# G3-Sensor.net
KiCad netlist of a schematic drawn in Altium Designer
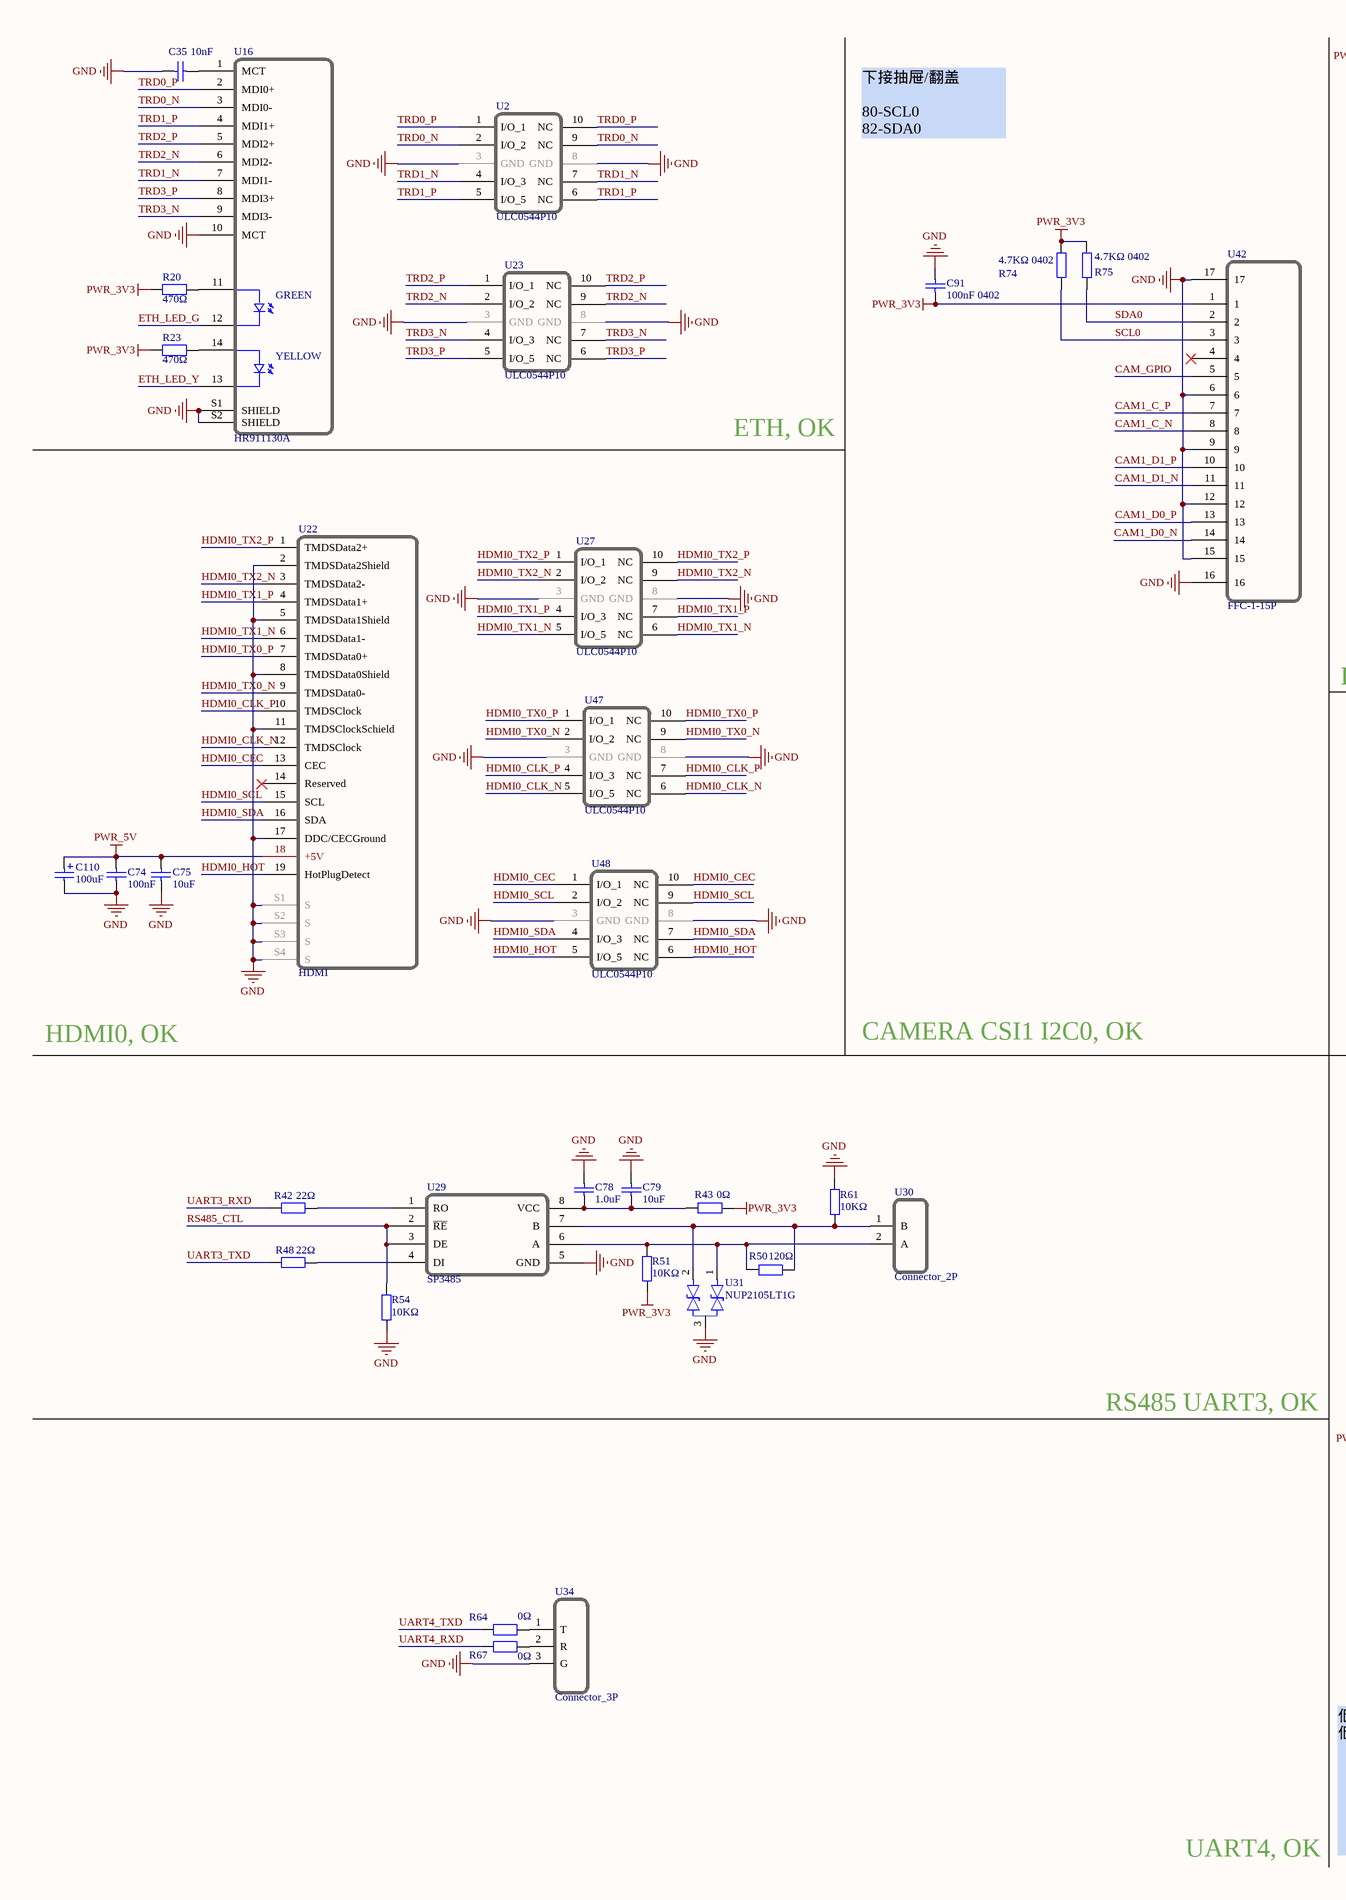
[diagram p0: G3-Sensor.SchDoc, left]
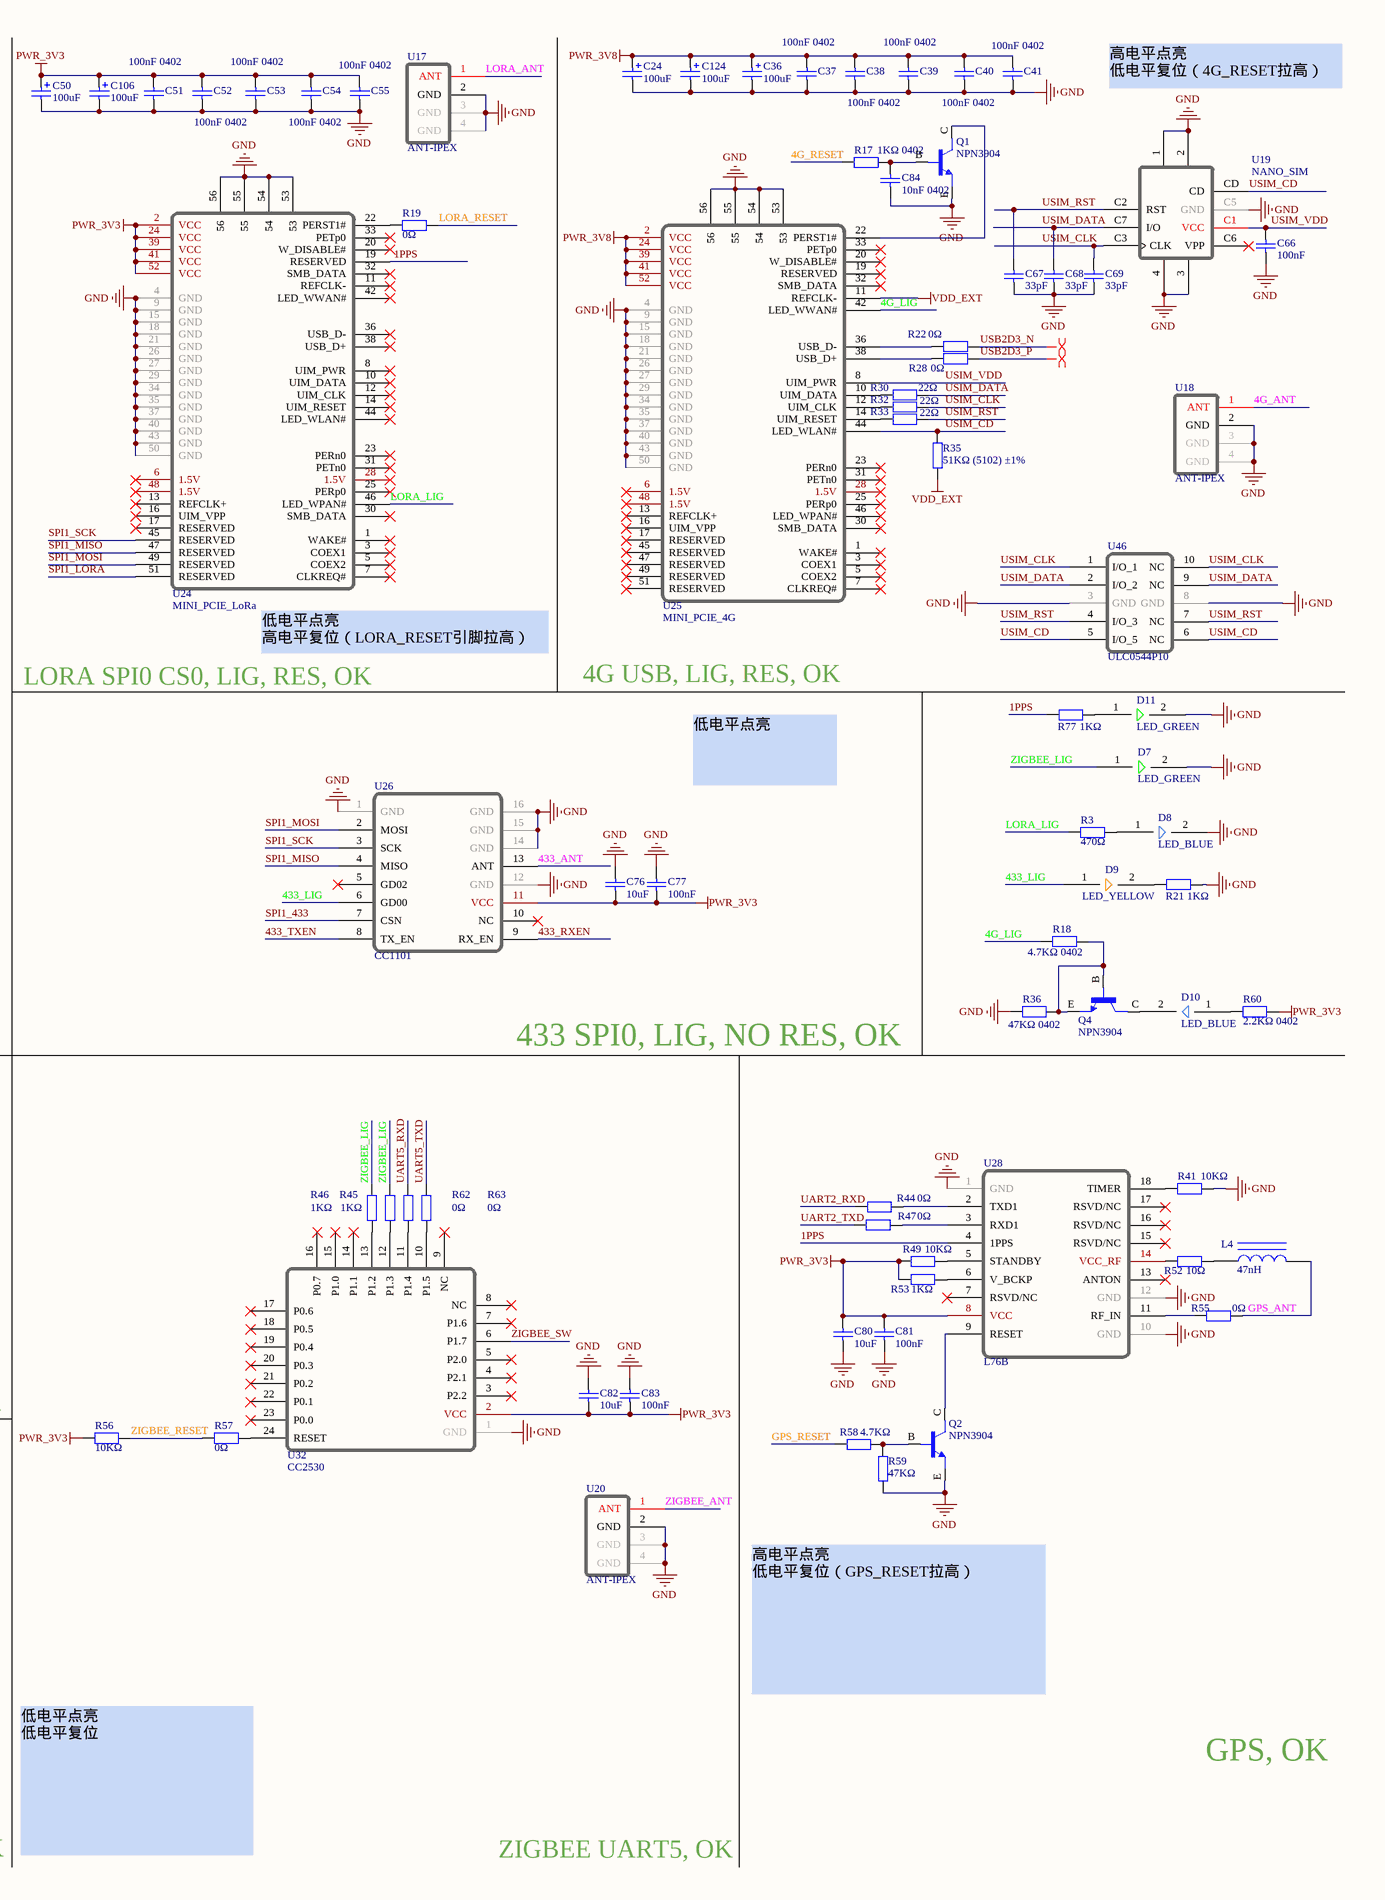
[diagram p1: G3-Sensor.SchDoc, right]

(export (version "E")
  (design (tool "Eeschema 10.0.6"))
  (components
    (comp (ref "C24")
      (value "100uF")
      (footprint "CASE-B_3528")
      (description "钽电容")
      (libsource (lib "Miscellaneous Devices LC") (part "3528 100uF (107) 10% 6.3V"))
    )
    (comp (ref "C35")
      (value "10nF")
      (footprint "0402_C")
      (description "贴片电容")
      (libsource (lib "Miscellaneous Devices LC") (part "0402 10nF (103) 10% 50V"))
    )
    (comp (ref "C36")
      (value "100uF")
      (footprint "CASE-B_3528")
      (description "钽电容")
      (libsource (lib "Miscellaneous Devices LC") (part "3528 100uF (107) 10% 6.3V"))
    )
    (comp (ref "C37")
      (value "100nF 0402")
      (footprint "0402_C")
      (description "贴片电容")
      (libsource (lib "Miscellaneous Devices LC") (part "0402 100nF (104) 10% 16V"))
    )
    (comp (ref "C38")
      (value "100nF 0402")
      (footprint "0402_C")
      (description "贴片电容")
      (libsource (lib "Miscellaneous Devices LC") (part "0402 100nF (104) 10% 16V"))
    )
    (comp (ref "C39")
      (value "100nF 0402")
      (footprint "0402_C")
      (description "贴片电容")
      (libsource (lib "Miscellaneous Devices LC") (part "0402 100nF (104) 10% 16V"))
    )
    (comp (ref "C40")
      (value "100nF 0402")
      (footprint "0402_C")
      (description "贴片电容")
      (libsource (lib "Miscellaneous Devices LC") (part "0402 100nF (104) 10% 16V"))
    )
    (comp (ref "C41")
      (value "100nF 0402")
      (footprint "0402_C")
      (description "贴片电容")
      (libsource (lib "Miscellaneous Devices LC") (part "0402 100nF (104) 10% 16V"))
    )
    (comp (ref "C50")
      (value "100uF")
      (footprint "CASE-B_3528")
      (description "钽电容")
      (libsource (lib "Miscellaneous Devices LC") (part "3528 100uF (107) 10% 6.3V"))
    )
    (comp (ref "C51")
      (value "100nF 0402")
      (footprint "0402_C")
      (description "贴片电容")
      (libsource (lib "Miscellaneous Devices LC") (part "0402 100nF (104) 10% 16V"))
    )
    (comp (ref "C52")
      (value "100nF 0402")
      (footprint "0402_C")
      (description "贴片电容")
      (libsource (lib "Miscellaneous Devices LC") (part "0402 100nF (104) 10% 16V"))
    )
    (comp (ref "C53")
      (value "100nF 0402")
      (footprint "0402_C")
      (description "贴片电容")
      (libsource (lib "Miscellaneous Devices LC") (part "0402 100nF (104) 10% 16V"))
    )
    (comp (ref "C54")
      (value "100nF 0402")
      (footprint "0402_C")
      (description "贴片电容")
      (libsource (lib "Miscellaneous Devices LC") (part "0402 100nF (104) 10% 16V"))
    )
    (comp (ref "C55")
      (value "100nF 0402")
      (footprint "0402_C")
      (description "贴片电容")
      (libsource (lib "Miscellaneous Devices LC") (part "0402 100nF (104) 10% 16V"))
    )
    (comp (ref "C66")
      (value "100nF")
      (footprint "0402_C")
      (description "贴片电容")
      (libsource (lib "Miscellaneous Devices LC") (part "0402 100nF (104) 10% 16V"))
    )
    (comp (ref "C67")
      (value "33pF")
      (footprint "0402_C")
      (description "贴片电容")
      (libsource (lib "Miscellaneous Devices LC") (part "0402 33pF (330) 5% 50V"))
    )
    (comp (ref "C68")
      (value "33pF")
      (footprint "0402_C")
      (description "贴片电容")
      (libsource (lib "Miscellaneous Devices LC") (part "0402 33pF (330) 5% 50V"))
    )
    (comp (ref "C69")
      (value "33pF")
      (footprint "0402_C")
      (description "贴片电容")
      (libsource (lib "Miscellaneous Devices LC") (part "0402 33pF (330) 5% 50V"))
    )
    (comp (ref "C74")
      (value "100nF")
      (footprint "0402_C")
      (description "贴片电容")
      (libsource (lib "Miscellaneous Devices LC") (part "0402 100nF (104) 10% 16V"))
    )
    (comp (ref "C75")
      (value "10uF")
      (footprint "0402_C")
      (description "贴片电容")
      (libsource (lib "Miscellaneous Devices LC") (part "0402 10uF (106) 20% 6.3V"))
    )
    (comp (ref "C76")
      (value "10uF")
      (footprint "0402_C")
      (description "贴片电容")
      (libsource (lib "Miscellaneous Devices LC") (part "0402 10uF (106) 20% 6.3V"))
    )
    (comp (ref "C77")
      (value "100nF")
      (footprint "0402_C")
      (description "贴片电容")
      (libsource (lib "Miscellaneous Devices LC") (part "0402 100nF (104) 10% 16V"))
    )
    (comp (ref "C78")
      (value "1.0uF")
      (footprint "0402_C")
      (description "贴片电容")
      (libsource (lib "Miscellaneous Devices LC") (part "0402 1.0uF (105) 10% 25V"))
    )
    (comp (ref "C79")
      (value "10uF")
      (footprint "0402_C")
      (description "贴片电容")
      (libsource (lib "Miscellaneous Devices LC") (part "0402 10uF (106) 20% 6.3V"))
    )
    (comp (ref "C80")
      (value "10uF")
      (footprint "0402_C")
      (description "贴片电容")
      (libsource (lib "Miscellaneous Devices LC") (part "0402 10uF (106) 20% 6.3V"))
    )
    (comp (ref "C81")
      (value "100nF")
      (footprint "0402_C")
      (description "贴片电容")
      (libsource (lib "Miscellaneous Devices LC") (part "0402 100nF (104) 10% 16V"))
    )
    (comp (ref "C82")
      (value "10uF")
      (footprint "0402_C")
      (description "贴片电容")
      (libsource (lib "Miscellaneous Devices LC") (part "0402 10uF (106) 20% 6.3V"))
    )
    (comp (ref "C83")
      (value "100nF")
      (footprint "0402_C")
      (description "贴片电容")
      (libsource (lib "Miscellaneous Devices LC") (part "0402 100nF (104) 10% 16V"))
    )
    (comp (ref "C84")
      (value "10nF 0402")
      (footprint "0402_C")
      (description "贴片电容")
      (libsource (lib "Miscellaneous Devices LC") (part "0402 10nF (103) 10% 50V"))
    )
    (comp (ref "C91")
      (value "100nF 0402")
      (footprint "0402_C")
      (description "贴片电容")
      (libsource (lib "Miscellaneous Devices LC") (part "0402 100nF (104) 10% 16V"))
    )
    (comp (ref "C106")
      (value "100uF")
      (footprint "CASE-B_3528")
      (description "钽电容")
      (libsource (lib "Miscellaneous Devices LC") (part "3528 100uF (107) 10% 6.3V"))
    )
    (comp (ref "C110")
      (value "100uF")
      (footprint "CASE-B_3528")
      (description "钽电容")
      (libsource (lib "Miscellaneous Devices LC") (part "3528 100uF (107) 10% 6.3V"))
    )
    (comp (ref "C124")
      (value "100uF")
      (footprint "CASE-B_3528")
      (description "钽电容")
      (libsource (lib "Miscellaneous Devices LC") (part "3528 100uF (107) 10% 6.3V"))
    )
    (comp (ref "D7")
      (value "LED_GREEN")
      (footprint "LED_SIDE")
      (description "LED GREEN 0603 SIDE")
      (libsource (lib "bohao") (part "LED_GREEN"))
    )
    (comp (ref "D8")
      (value "LED_BLUE")
      (footprint "LED_SIDE")
      (description "LED BLUE 0603 SIDE")
      (libsource (lib "bohao") (part "LED_BLUE"))
    )
    (comp (ref "D9")
      (value "LED_YELLOW")
      (footprint "LED_SIDE")
      (description "LED YELLOW 0603 SIDE")
      (libsource (lib "bohao") (part "LED_YELLOW"))
    )
    (comp (ref "D10")
      (value "LED_BLUE")
      (footprint "LED_SIDE")
      (description "LED BLUE 0603 SIDE")
      (libsource (lib "bohao") (part "LED_BLUE"))
    )
    (comp (ref "D11")
      (value "LED_GREEN")
      (footprint "LED_SIDE")
      (description "LED GREEN 0603 SIDE")
      (libsource (lib "bohao") (part "LED_GREEN"))
    )
    (comp (ref "L4")
      (value "47nH")
      (footprint "0603_L")
      (description "贴片电感")
      (libsource (lib "Miscellaneous Devices LC") (part "0603 47nH"))
    )
    (comp (ref "Q1")
      (value "NPN3904")
      (footprint "NPN3904")
      (description "NPN 40V 200mA 300MHz 300mW Surface")
      (fields (field (name "MF") "ON Semiconductor") (field (name "MP") "MMBT3904LT1G"))
      (libsource (lib "") (part "NPN3904_1"))
    )
    (comp (ref "Q2")
      (value "NPN3904")
      (footprint "NPN3904")
      (description "NPN 40V 200mA 300MHz 300mW Surface")
      (fields (field (name "MF") "ON Semiconductor") (field (name "MP") "MMBT3904LT1G"))
      (libsource (lib "") (part "NPN3904_1"))
    )
    (comp (ref "Q4")
      (value "NPN3904")
      (footprint "NPN3904")
      (description "NPN 40V 200mA 300MHz 300mW Surface")
      (fields (field (name "MF") "ON Semiconductor") (field (name "MP") "MMBT3904LT1G"))
      (libsource (lib "bohao") (part "NPN3904"))
    )
    (comp (ref "R3")
      (value "470Ω")
      (footprint "0402_R")
      (description "贴片电阻")
      (libsource (lib "Miscellaneous Devices LC") (part "0402 470Ω (4700) 1%"))
    )
    (comp (ref "R17")
      (value "1KΩ 0402")
      (footprint "0402_R")
      (description "贴片电阻")
      (libsource (lib "Miscellaneous Devices LC") (part "0402 1KΩ (1001) 1%"))
    )
    (comp (ref "R18")
      (value "4.7KΩ 0402")
      (footprint "0402_R")
      (description "贴片电阻")
      (libsource (lib "Miscellaneous Devices LC") (part "0402 4.7KΩ (4701) 1%"))
    )
    (comp (ref "R19")
      (value "0Ω")
      (footprint "0402_R")
      (description "贴片电阻")
      (libsource (lib "") (part "0402 0Ω (0R0) 1%_1"))
    )
    (comp (ref "R20")
      (value "470Ω")
      (footprint "0402_R")
      (description "贴片电阻")
      (libsource (lib "Miscellaneous Devices LC") (part "0402 470Ω (4700) 1%"))
    )
    (comp (ref "R21")
      (value "1KΩ")
      (footprint "0402_R")
      (description "贴片电阻")
      (libsource (lib "Miscellaneous Devices LC") (part "0402 1KΩ (1001) 1%"))
    )
    (comp (ref "R22")
      (value "0Ω")
      (footprint "0402_R")
      (description "贴片电阻")
      (libsource (lib "") (part "0402 0Ω (0R0) 1%_1"))
    )
    (comp (ref "R23")
      (value "470Ω")
      (footprint "0402_R")
      (description "贴片电阻")
      (libsource (lib "Miscellaneous Devices LC") (part "0402 470Ω (4700) 1%"))
    )
    (comp (ref "R28")
      (value "0Ω")
      (footprint "0402_R")
      (description "贴片电阻")
      (libsource (lib "Miscellaneous Devices LC") (part "0402 0Ω (0R0) 1%"))
    )
    (comp (ref "R30")
      (value "22Ω")
      (footprint "0402_R")
      (description "贴片电阻")
      (libsource (lib "Miscellaneous Devices LC") (part "0402 22Ω (22R0) 1%"))
    )
    (comp (ref "R32")
      (value "22Ω")
      (footprint "0402_R")
      (description "贴片电阻")
      (libsource (lib "Miscellaneous Devices LC") (part "0402 22Ω (22R0) 1%"))
    )
    (comp (ref "R33")
      (value "22Ω")
      (footprint "0402_R")
      (description "贴片电阻")
      (libsource (lib "Miscellaneous Devices LC") (part "0402 22Ω (22R0) 1%"))
    )
    (comp (ref "R35")
      (value "51KΩ (5102) ±1%")
      (footprint "0402_R")
      (description "贴片电阻")
      (libsource (lib "Miscellaneous Devices LC") (part "0402 51KΩ (5102) 1%"))
    )
    (comp (ref "R36")
      (value "47KΩ 0402")
      (footprint "0402_R")
      (description "贴片电阻")
      (libsource (lib "") (part "0402 47KΩ (4702) 1%_1"))
    )
    (comp (ref "R41")
      (value "10KΩ")
      (footprint "0402_R")
      (description "贴片电阻")
      (libsource (lib "") (part "0402 10KΩ (1002) 1%_1"))
    )
    (comp (ref "R42")
      (value "22Ω")
      (footprint "0402_R")
      (description "贴片电阻")
      (libsource (lib "Miscellaneous Devices LC") (part "0402 22Ω (22R0) 1%"))
    )
    (comp (ref "R43")
      (value "0Ω")
      (footprint "0402_R")
      (description "贴片电阻")
      (libsource (lib "Miscellaneous Devices LC") (part "0402 0Ω (0R0) 1%"))
    )
    (comp (ref "R44")
      (value "0Ω")
      (footprint "0402_R")
      (description "贴片电阻")
      (libsource (lib "Miscellaneous Devices LC") (part "0402 0Ω (0R0) 1%"))
    )
    (comp (ref "R45")
      (value "1KΩ")
      (footprint "0402_R")
      (description "贴片电阻")
      (libsource (lib "") (part "0402 1KΩ (1001) 1%_1"))
    )
    (comp (ref "R46")
      (value "1KΩ")
      (footprint "0402_R")
      (description "贴片电阻")
      (libsource (lib "") (part "0402 1KΩ (1001) 1%_1"))
    )
    (comp (ref "R47")
      (value "0Ω")
      (footprint "0402_R")
      (description "贴片电阻")
      (libsource (lib "Miscellaneous Devices LC") (part "0402 0Ω (0R0) 1%"))
    )
    (comp (ref "R48")
      (value "22Ω")
      (footprint "0402_R")
      (description "贴片电阻")
      (libsource (lib "Miscellaneous Devices LC") (part "0402 22Ω (22R0) 1%"))
    )
    (comp (ref "R49")
      (value "10KΩ")
      (footprint "0402_R")
      (description "贴片电阻")
      (libsource (lib "") (part "0402 10KΩ (1002) 1%_1"))
    )
    (comp (ref "R50")
      (value "120Ω")
      (footprint "0402_R")
      (description "贴片电阻")
      (libsource (lib "Miscellaneous Devices LC") (part "0402 120Ω (1200) 1%"))
    )
    (comp (ref "R51")
      (value "10KΩ")
      (footprint "0402_R")
      (description "贴片电阻")
      (libsource (lib "Miscellaneous Devices LC") (part "0402 10KΩ (1002) 1%"))
    )
    (comp (ref "R52")
      (value "10Ω")
      (footprint "0402_R")
      (description "贴片电阻")
      (libsource (lib "Miscellaneous Devices LC") (part "0402 10Ω (10R0) 1%"))
    )
    (comp (ref "R53")
      (value "1KΩ")
      (footprint "0402_R")
      (description "贴片电阻")
      (libsource (lib "Miscellaneous Devices LC") (part "0402 1KΩ (1001) 1%"))
    )
    (comp (ref "R54")
      (value "10KΩ")
      (footprint "0402_R")
      (description "贴片电阻")
      (libsource (lib "Miscellaneous Devices LC") (part "0402 10KΩ (1002) 1%"))
    )
    (comp (ref "R55")
      (value "0Ω")
      (footprint "0402_R")
      (description "贴片电阻")
      (libsource (lib "Miscellaneous Devices LC") (part "0402 0Ω (0R0) 1%"))
    )
    (comp (ref "R56")
      (value "10KΩ")
      (footprint "0402_R")
      (description "贴片电阻")
      (libsource (lib "") (part "0402 10KΩ (1002) 1%_1"))
    )
    (comp (ref "R57")
      (value "0Ω")
      (footprint "0402_R")
      (description "贴片电阻")
      (libsource (lib "") (part "0402 0Ω (0R0) 1%_1"))
    )
    (comp (ref "R58")
      (value "4.7KΩ")
      (footprint "0402_R")
      (description "贴片电阻")
      (libsource (lib "Miscellaneous Devices LC") (part "0402 4.7KΩ (4701) 1%"))
    )
    (comp (ref "R59")
      (value "47KΩ")
      (footprint "0402_R")
      (description "贴片电阻")
      (libsource (lib "Miscellaneous Devices LC") (part "0402 47KΩ (4702) 1%"))
    )
    (comp (ref "R60")
      (value "2.2KΩ 0402")
      (footprint "0402_R")
      (description "贴片电阻")
      (libsource (lib "Miscellaneous Devices LC") (part "0402 2.2KΩ (2201) 1%"))
    )
    (comp (ref "R61")
      (value "10KΩ")
      (footprint "0402_R")
      (description "贴片电阻")
      (libsource (lib "Miscellaneous Devices LC") (part "0402 10KΩ (1002) 1%"))
    )
    (comp (ref "R62")
      (value "0Ω")
      (footprint "0402_R")
      (description "贴片电阻")
      (libsource (lib "") (part "0402 0Ω (0R0) 1%_2"))
    )
    (comp (ref "R63")
      (value "0Ω")
      (footprint "0402_R")
      (description "贴片电阻")
      (libsource (lib "") (part "0402 0Ω (0R0) 1%_2"))
    )
    (comp (ref "R64")
      (value "0Ω")
      (footprint "0402_R")
      (description "贴片电阻")
      (libsource (lib "") (part "0402 0Ω (0R0) 1%_1"))
    )
    (comp (ref "R67")
      (value "0Ω")
      (footprint "0402_R")
      (description "贴片电阻")
      (libsource (lib "") (part "0402 0Ω (0R0) 1%_1"))
    )
    (comp (ref "R74")
      (value "4.7KΩ 0402")
      (footprint "0402_R")
      (description "贴片电阻")
      (libsource (lib "") (part "0402 4.7KΩ (4701) 1%_1"))
    )
    (comp (ref "R75")
      (value "4.7KΩ 0402")
      (footprint "0402_R")
      (description "贴片电阻")
      (libsource (lib "") (part "0402 4.7KΩ (4701) 1%_1"))
    )
    (comp (ref "R77")
      (value "1KΩ")
      (footprint "0402_R")
      (description "贴片电阻")
      (libsource (lib "Miscellaneous Devices LC") (part "0402 1KΩ (1001) 1%"))
    )
    (comp (ref "U2")
      (value "ULC0544P10")
      (footprint "ULC0544P10")
      (description "ESD")
      (libsource (lib "bohao") (part "ULC0544P10"))
    )
    (comp (ref "U16")
      (value "HR911130A")
      (footprint "HR911130A")
      (description "ETH RJ45")
      (libsource (lib "bohao") (part "HR911130A"))
    )
    (comp (ref "U17")
      (value "ANT-IPEX")
      (footprint "ANT-IPEX")
      (description "ANT")
      (libsource (lib "bohao") (part "ANT-IPEX"))
    )
    (comp (ref "U18")
      (value "ANT-IPEX")
      (footprint "ANT-IPEX")
      (description "ANT")
      (libsource (lib "bohao") (part "ANT-IPEX"))
    )
    (comp (ref "U19")
      (value "NANO_SIM")
      (footprint "NANO_SIM")
      (description "4G Card Slot")
      (libsource (lib "bohao") (part "NANO_SIM"))
    )
    (comp (ref "U20")
      (value "ANT-IPEX")
      (footprint "ANT-IPEX")
      (description "ANT")
      (libsource (lib "bohao") (part "ANT-IPEX"))
    )
    (comp (ref "U22") (value "HDMI") (footprint "HDMI") (libsource (lib "bohao") (part "HDMI")))
    (comp (ref "U23")
      (value "ULC0544P10")
      (footprint "ULC0544P10")
      (description "ESD")
      (libsource (lib "bohao") (part "ULC0544P10"))
    )
    (comp (ref "U24")
      (value "MINI_PCIE_LoRa")
      (footprint "MINI-PCIE")
      (description "LoRa, 4G")
      (libsource (lib "bohao") (part "MINI_PCIE"))
    )
    (comp (ref "U25")
      (value "MINI_PCIE_4G")
      (footprint "MINI-PCIE")
      (description "LoRa, 4G")
      (libsource (lib "bohao") (part "MINI_PCIE"))
    )
    (comp (ref "U26")
      (value "CC1101")
      (footprint "CC1101")
      (description "433Mhz")
      (libsource (lib "bohao") (part "CC1101"))
    )
    (comp (ref "U27")
      (value "ULC0544P10")
      (footprint "ULC0544P10")
      (description "ESD")
      (libsource (lib "bohao") (part "ULC0544P10"))
    )
    (comp (ref "U28")
      (value "L76B")
      (footprint "L76B")
      (description "GPS BEIDOU")
      (libsource (lib "bohao") (part "L76B"))
    )
    (comp (ref "U29")
      (value "SP3485")
      (footprint "SP3485")
      (description "UART = RS485")
      (libsource (lib "bohao") (part "SP3485"))
    )
    (comp (ref "U30")
      (value "Connector_2P")
      (footprint "CONNECTOR_2P")
      (description "Connector for RS485, CAN")
      (libsource (lib "bohao") (part "Connector_2P"))
    )
    (comp (ref "U31")
      (value "NUP2105LT1G")
      (footprint "NUP2105LT1G")
      (libsource (lib "bohao") (part "NUP2105LT1G"))
    )
    (comp (ref "U32")
      (value "CC2530")
      (footprint "CC2530")
      (description "ZigBee 2.4GHz")
      (libsource (lib "bohao") (part "CC2530"))
    )
    (comp (ref "U34")
      (value "Connector_3P")
      (footprint "CONNECTOR_3P")
      (description "Connector for UART")
      (libsource (lib "bohao") (part "Connector_3P"))
    )
    (comp (ref "U42")
      (value "FFC-1-15P")
      (footprint "FFC-1-15P")
      (description "1.0MM 15PIN")
      (libsource (lib "bohao") (part "FFC-1-15P"))
    )
    (comp (ref "U46")
      (value "ULC0544P10")
      (footprint "ULC0544P10")
      (description "ESD")
      (libsource (lib "bohao") (part "ULC0544P10"))
    )
    (comp (ref "U47")
      (value "ULC0544P10")
      (footprint "ULC0544P10")
      (description "ESD")
      (libsource (lib "bohao") (part "ULC0544P10"))
    )
    (comp (ref "U48")
      (value "ULC0544P10")
      (footprint "ULC0544P10")
      (description "ESD")
      (libsource (lib "bohao") (part "ULC0544P10"))
    )
  )
  (nets
    (net (code "1") (name "/1PPS") (class "Default")
      (node (ref "R77") (pin "1") (pinfunction "1_1") (pintype "passive"))
      (node (ref "U24") (pin "19") (pinfunction "RESERVED_19") (pintype "passive"))
      (node (ref "U28") (pin "4") (pinfunction "1PPS_4") (pintype "passive"))
    )
    (net (code "2") (name "/4G_ANT") (class "Default")
      (node (ref "U18") (pin "1") (pinfunction "ANT_1") (pintype "passive"))
    )
    (net (code "3") (name "/4G_LIG") (class "Default")
      (node (ref "R18") (pin "1") (pinfunction "1_1") (pintype "passive"))
      (node (ref "U25") (pin "42") (pinfunction "LED_WWAN#_42") (pintype "passive"))
    )
    (net (code "4") (name "/4G_RESET") (class "Default")
      (node (ref "R17") (pin "1") (pinfunction "1_1") (pintype "passive"))
    )
    (net (code "5") (name "/433_ANT") (class "Default")
      (node (ref "U26") (pin "13") (pinfunction "ANT_13") (pintype "passive"))
    )
    (net (code "6") (name "/433_LIG") (class "Default")
      (node (ref "D9") (pin "1") (pintype "passive"))
      (node (ref "U26") (pin "6") (pinfunction "GD00_6") (pintype "passive"))
    )
    (net (code "7") (name "/433_RXEN") (class "Default")
      (node (ref "U26") (pin "9") (pinfunction "RX_EN_9") (pintype "passive"))
    )
    (net (code "8") (name "/433_TXEN") (class "Default")
      (node (ref "U26") (pin "8") (pinfunction "TX_EN_8") (pintype "passive"))
    )
    (net (code "9") (name "/CAM1_C_N") (class "Default")
      (node (ref "U42") (pin "8") (pinfunction "8_8") (pintype "passive"))
    )
    (net (code "10") (name "/CAM1_C_P") (class "Default")
      (node (ref "U42") (pin "7") (pinfunction "7_7") (pintype "passive"))
    )
    (net (code "11") (name "/CAM1_D0_N") (class "Default")
      (node (ref "U42") (pin "14") (pinfunction "14_14") (pintype "passive"))
    )
    (net (code "12") (name "/CAM1_D0_P") (class "Default")
      (node (ref "U42") (pin "13") (pinfunction "13_13") (pintype "passive"))
    )
    (net (code "13") (name "/CAM1_D1_N") (class "Default")
      (node (ref "U42") (pin "11") (pinfunction "11_11") (pintype "passive"))
    )
    (net (code "14") (name "/CAM1_D1_P") (class "Default")
      (node (ref "U42") (pin "10") (pinfunction "10_10") (pintype "passive"))
    )
    (net (code "15") (name "/CAM_GPIO") (class "Default")
      (node (ref "U42") (pin "5") (pinfunction "5_5") (pintype "passive"))
    )
    (net (code "16") (name "/ETH_LED_G") (class "Default")
      (node (ref "U16") (pin "12") (pinfunction "12_12") (pintype "passive"))
    )
    (net (code "17") (name "/ETH_LED_Y") (class "Default")
      (node (ref "U16") (pin "13") (pinfunction "13_13") (pintype "passive"))
    )
    (net (code "18") (name "/GPS_ANT") (class "Default")
      (node (ref "L4") (pin "2") (pinfunction "2_2") (pintype "passive"))
      (node (ref "R55") (pin "2") (pinfunction "2_2") (pintype "passive"))
    )
    (net (code "19") (name "/GPS_RESET") (class "Default")
      (node (ref "R58") (pin "1") (pinfunction "1_1") (pintype "passive"))
    )
    (net (code "20") (name "/HDMI0_CEC") (class "Default")
      (node (ref "U22") (pin "13") (pinfunction "CEC_13") (pintype "passive"))
      (node (ref "U48") (pin "1") (pinfunction "I/O_1_1") (pintype "passive"))
      (node (ref "U48") (pin "10") (pinfunction "NC_10") (pintype "passive"))
    )
    (net (code "21") (name "/HDMI0_CLK_N") (class "Default")
      (node (ref "U22") (pin "12") (pinfunction "TMDSClock_12") (pintype "passive"))
      (node (ref "U47") (pin "5") (pinfunction "I/O_5_5") (pintype "passive"))
      (node (ref "U47") (pin "6") (pinfunction "NC_6") (pintype "passive"))
    )
    (net (code "22") (name "/HDMI0_CLK_P") (class "Default")
      (node (ref "U22") (pin "10") (pinfunction "TMDSClock_10") (pintype "passive"))
      (node (ref "U47") (pin "4") (pinfunction "I/O_3_4") (pintype "passive"))
      (node (ref "U47") (pin "7") (pinfunction "NC_7") (pintype "passive"))
    )
    (net (code "23") (name "/HDMI0_HOT") (class "Default")
      (node (ref "U22") (pin "19") (pinfunction "HotPlugDetect_19") (pintype "passive"))
      (node (ref "U48") (pin "5") (pinfunction "I/O_5_5") (pintype "passive"))
      (node (ref "U48") (pin "6") (pinfunction "NC_6") (pintype "passive"))
    )
    (net (code "24") (name "/HDMI0_SCL") (class "Default")
      (node (ref "U22") (pin "15") (pinfunction "SCL_15") (pintype "passive"))
      (node (ref "U48") (pin "2") (pinfunction "I/O_2_2") (pintype "passive"))
      (node (ref "U48") (pin "9") (pinfunction "NC_9") (pintype "passive"))
    )
    (net (code "25") (name "/HDMI0_SDA") (class "Default")
      (node (ref "U22") (pin "16") (pinfunction "SDA_16") (pintype "passive"))
      (node (ref "U48") (pin "4") (pinfunction "I/O_3_4") (pintype "passive"))
      (node (ref "U48") (pin "7") (pinfunction "NC_7") (pintype "passive"))
    )
    (net (code "26") (name "/HDMI0_TX0_N") (class "Default")
      (node (ref "U22") (pin "9") (pinfunction "TMDSData0-_9") (pintype "passive"))
      (node (ref "U47") (pin "2") (pinfunction "I/O_2_2") (pintype "passive"))
      (node (ref "U47") (pin "9") (pinfunction "NC_9") (pintype "passive"))
    )
    (net (code "27") (name "/HDMI0_TX0_P") (class "Default")
      (node (ref "U22") (pin "7") (pinfunction "TMDSData0+_7") (pintype "passive"))
      (node (ref "U47") (pin "1") (pinfunction "I/O_1_1") (pintype "passive"))
      (node (ref "U47") (pin "10") (pinfunction "NC_10") (pintype "passive"))
    )
    (net (code "28") (name "/HDMI0_TX1_N") (class "Default")
      (node (ref "U22") (pin "6") (pinfunction "TMDSData1-_6") (pintype "passive"))
      (node (ref "U27") (pin "5") (pinfunction "I/O_5_5") (pintype "passive"))
      (node (ref "U27") (pin "6") (pinfunction "NC_6") (pintype "passive"))
    )
    (net (code "29") (name "/HDMI0_TX1_P") (class "Default")
      (node (ref "U22") (pin "4") (pinfunction "TMDSData1+_4") (pintype "passive"))
      (node (ref "U27") (pin "4") (pinfunction "I/O_3_4") (pintype "passive"))
      (node (ref "U27") (pin "7") (pinfunction "NC_7") (pintype "passive"))
    )
    (net (code "30") (name "/HDMI0_TX2_N") (class "Default")
      (node (ref "U22") (pin "3") (pinfunction "TMDSData2-_3") (pintype "passive"))
      (node (ref "U27") (pin "2") (pinfunction "I/O_2_2") (pintype "passive"))
      (node (ref "U27") (pin "9") (pinfunction "NC_9") (pintype "passive"))
    )
    (net (code "31") (name "/HDMI0_TX2_P") (class "Default")
      (node (ref "U22") (pin "1") (pinfunction "TMDSData2+_1") (pintype "passive"))
      (node (ref "U27") (pin "1") (pinfunction "I/O_1_1") (pintype "passive"))
      (node (ref "U27") (pin "10") (pinfunction "NC_10") (pintype "passive"))
    )
    (net (code "32") (name "/LORA_ANT") (class "Default")
      (node (ref "U17") (pin "1") (pinfunction "ANT_1") (pintype "passive"))
    )
    (net (code "33") (name "/LORA_LIG") (class "Default")
      (node (ref "R3") (pin "1") (pinfunction "1_1") (pintype "passive"))
      (node (ref "U24") (pin "46") (pinfunction "LED_WPAN#_46") (pintype "passive"))
    )
    (net (code "34") (name "/LORA_RESET") (class "Default")
      (node (ref "R19") (pin "1") (pinfunction "1_1") (pintype "passive"))
    )
    (net (code "35") (name "/RS485_CTL") (class "Default")
      (node (ref "R54") (pin "2") (pinfunction "2_2") (pintype "passive"))
      (node (ref "U29") (pin "2") (pinfunction "~{RE}_2") (pintype "passive"))
      (node (ref "U29") (pin "3") (pinfunction "DE_3") (pintype "passive"))
    )
    (net (code "36") (name "/SCL0") (class "Default")
      (node (ref "R74") (pin "1") (pinfunction "1_1") (pintype "passive"))
      (node (ref "U42") (pin "3") (pinfunction "3_3") (pintype "passive"))
    )
    (net (code "37") (name "/SDA0") (class "Default")
      (node (ref "R75") (pin "1") (pinfunction "1_1") (pintype "passive"))
      (node (ref "U42") (pin "2") (pinfunction "2_2") (pintype "passive"))
    )
    (net (code "38") (name "/SPI1_433") (class "Default")
      (node (ref "U26") (pin "7") (pinfunction "CSN_7") (pintype "passive"))
    )
    (net (code "39") (name "/SPI1_LORA") (class "Default")
      (node (ref "U24") (pin "51") (pinfunction "RESERVED_51") (pintype "passive"))
    )
    (net (code "40") (name "/SPI1_MISO") (class "Default")
      (node (ref "U24") (pin "47") (pinfunction "RESERVED_47") (pintype "passive"))
      (node (ref "U26") (pin "4") (pinfunction "MISO_4") (pintype "passive"))
    )
    (net (code "41") (name "/SPI1_MOSI") (class "Default")
      (node (ref "U24") (pin "49") (pinfunction "RESERVED_49") (pintype "passive"))
      (node (ref "U26") (pin "2") (pinfunction "MOSI_2") (pintype "passive"))
    )
    (net (code "42") (name "/SPI1_SCK") (class "Default")
      (node (ref "U24") (pin "45") (pinfunction "RESERVED_45") (pintype "passive"))
      (node (ref "U26") (pin "3") (pinfunction "SCK_3") (pintype "passive"))
    )
    (net (code "43") (name "/TRD0_N") (class "Default")
      (node (ref "U16") (pin "3") (pinfunction "MDI0-_3") (pintype "passive"))
      (node (ref "U2") (pin "2") (pinfunction "I/O_2_2") (pintype "passive"))
      (node (ref "U2") (pin "9") (pinfunction "NC_9") (pintype "passive"))
    )
    (net (code "44") (name "/TRD0_P") (class "Default")
      (node (ref "U16") (pin "2") (pinfunction "MDI0+_2") (pintype "passive"))
      (node (ref "U2") (pin "1") (pinfunction "I/O_1_1") (pintype "passive"))
      (node (ref "U2") (pin "10") (pinfunction "NC_10") (pintype "passive"))
    )
    (net (code "45") (name "/TRD1_N") (class "Default")
      (node (ref "U16") (pin "7") (pinfunction "MDI1-_7") (pintype "passive"))
      (node (ref "U2") (pin "4") (pinfunction "I/O_3_4") (pintype "passive"))
      (node (ref "U2") (pin "7") (pinfunction "NC_7") (pintype "passive"))
    )
    (net (code "46") (name "/TRD1_P") (class "Default")
      (node (ref "U16") (pin "4") (pinfunction "MDI1+_4") (pintype "passive"))
      (node (ref "U2") (pin "5") (pinfunction "I/O_5_5") (pintype "passive"))
      (node (ref "U2") (pin "6") (pinfunction "NC_6") (pintype "passive"))
    )
    (net (code "47") (name "/TRD2_N") (class "Default")
      (node (ref "U16") (pin "6") (pinfunction "MDI2-_6") (pintype "passive"))
      (node (ref "U23") (pin "2") (pinfunction "I/O_2_2") (pintype "passive"))
      (node (ref "U23") (pin "9") (pinfunction "NC_9") (pintype "passive"))
    )
    (net (code "48") (name "/TRD2_P") (class "Default")
      (node (ref "U16") (pin "5") (pinfunction "MDI2+_5") (pintype "passive"))
      (node (ref "U23") (pin "1") (pinfunction "I/O_1_1") (pintype "passive"))
      (node (ref "U23") (pin "10") (pinfunction "NC_10") (pintype "passive"))
    )
    (net (code "49") (name "/TRD3_N") (class "Default")
      (node (ref "U16") (pin "9") (pinfunction "MDI3-_9") (pintype "passive"))
      (node (ref "U23") (pin "4") (pinfunction "I/O_3_4") (pintype "passive"))
      (node (ref "U23") (pin "7") (pinfunction "NC_7") (pintype "passive"))
    )
    (net (code "50") (name "/TRD3_P") (class "Default")
      (node (ref "U16") (pin "8") (pinfunction "MDI3+_8") (pintype "passive"))
      (node (ref "U23") (pin "5") (pinfunction "I/O_5_5") (pintype "passive"))
      (node (ref "U23") (pin "6") (pinfunction "NC_6") (pintype "passive"))
    )
    (net (code "51") (name "/UART2_RXD") (class "Default")
      (node (ref "R44") (pin "1") (pinfunction "1_1") (pintype "passive"))
    )
    (net (code "52") (name "/UART2_TXD") (class "Default")
      (node (ref "R47") (pin "1") (pinfunction "1_1") (pintype "passive"))
    )
    (net (code "53") (name "/UART3_RXD") (class "Default")
      (node (ref "R42") (pin "1") (pinfunction "1_1") (pintype "passive"))
    )
    (net (code "54") (name "/UART3_TXD") (class "Default")
      (node (ref "R48") (pin "1") (pinfunction "1_1") (pintype "passive"))
    )
    (net (code "55") (name "/UART4_RXD") (class "Default")
      (node (ref "R67") (pin "2") (pinfunction "2_2") (pintype "passive"))
    )
    (net (code "56") (name "/UART4_TXD") (class "Default")
      (node (ref "R64") (pin "2") (pinfunction "2_2") (pintype "passive"))
    )
    (net (code "57") (name "/UART5_RXD") (class "Default")
      (node (ref "R62") (pin "2") (pinfunction "2_2") (pintype "passive"))
    )
    (net (code "58") (name "/UART5_TXD") (class "Default")
      (node (ref "R63") (pin "2") (pinfunction "2_2") (pintype "passive"))
    )
    (net (code "59") (name "/USB2D3_N") (class "Default")
      (node (ref "R22") (pin "1") (pinfunction "1_1") (pintype "passive"))
    )
    (net (code "60") (name "/USB2D3_P") (class "Default")
      (node (ref "R28") (pin "2") (pinfunction "2_2") (pintype "passive"))
    )
    (net (code "61") (name "/USIM_CD") (class "Default")
      (node (ref "R35") (pin "2") (pinfunction "2_2") (pintype "passive"))
      (node (ref "U19") (pin "CD") (pinfunction "CD_CD") (pintype "passive"))
      (node (ref "U25") (pin "44") (pinfunction "LED_WLAN#_44") (pintype "passive"))
      (node (ref "U46") (pin "5") (pinfunction "I/O_5_5") (pintype "passive"))
      (node (ref "U46") (pin "6") (pinfunction "NC_6") (pintype "passive"))
    )
    (net (code "62") (name "/USIM_CLK") (class "Default")
      (node (ref "C69") (pin "2") (pinfunction "2_2") (pintype "passive"))
      (node (ref "R32") (pin "2") (pinfunction "2_2") (pintype "passive"))
      (node (ref "U19") (pin "C3") (pinfunction "CLK_C3") (pintype "passive"))
      (node (ref "U46") (pin "1") (pinfunction "I/O_1_1") (pintype "passive"))
      (node (ref "U46") (pin "10") (pinfunction "NC_10") (pintype "passive"))
    )
    (net (code "63") (name "/USIM_DATA") (class "Default")
      (node (ref "C68") (pin "2") (pinfunction "2_2") (pintype "passive"))
      (node (ref "R30") (pin "2") (pinfunction "2_2") (pintype "passive"))
      (node (ref "U19") (pin "C7") (pinfunction "I/O_C7") (pintype "passive"))
      (node (ref "U46") (pin "2") (pinfunction "I/O_2_2") (pintype "passive"))
      (node (ref "U46") (pin "9") (pinfunction "NC_9") (pintype "passive"))
    )
    (net (code "64") (name "/USIM_RST") (class "Default")
      (node (ref "C67") (pin "2") (pinfunction "2_2") (pintype "passive"))
      (node (ref "R33") (pin "2") (pinfunction "2_2") (pintype "passive"))
      (node (ref "U19") (pin "C2") (pinfunction "RST_C2") (pintype "passive"))
      (node (ref "U46") (pin "4") (pinfunction "I/O_3_4") (pintype "passive"))
      (node (ref "U46") (pin "7") (pinfunction "NC_7") (pintype "passive"))
    )
    (net (code "65") (name "/USIM_VDD") (class "Default")
      (node (ref "C66") (pin "2") (pinfunction "2_2") (pintype "passive"))
      (node (ref "U19") (pin "C1") (pinfunction "VCC_C1") (pintype "passive"))
      (node (ref "U25") (pin "8") (pinfunction "UIM_PWR_8") (pintype "passive"))
    )
    (net (code "66") (name "/ZIGBEE_ANT") (class "Default")
      (node (ref "U20") (pin "1") (pinfunction "ANT_1") (pintype "passive"))
    )
    (net (code "67") (name "/ZIGBEE_LIG") (class "Default")
      (node (ref "D7") (pin "1") (pintype "passive"))
      (node (ref "R45") (pin "2") (pinfunction "2_2") (pintype "passive"))
      (node (ref "R46") (pin "2") (pinfunction "2_2") (pintype "passive"))
    )
    (net (code "68") (name "/ZIGBEE_RESET") (class "Default")
      (node (ref "R56") (pin "2") (pinfunction "2_2") (pintype "passive"))
      (node (ref "R57") (pin "2") (pinfunction "2_2") (pintype "passive"))
    )
    (net (code "69") (name "/ZIGBEE_SW") (class "Default")
      (node (ref "U32") (pin "6") (pinfunction "P1.7_6") (pintype "passive"))
    )
    (net (code "70") (name "GND") (class "Default")
      (node (ref "C106") (pin "2") (pinfunction "2_2") (pintype "passive"))
      (node (ref "C110") (pin "2") (pinfunction "2_2") (pintype "passive"))
      (node (ref "C124") (pin "2") (pinfunction "2_2") (pintype "passive"))
      (node (ref "C24") (pin "2") (pinfunction "2_2") (pintype "passive"))
      (node (ref "C35") (pin "1") (pinfunction "1_1") (pintype "passive"))
      (node (ref "C36") (pin "2") (pinfunction "2_2") (pintype "passive"))
      (node (ref "C37") (pin "1") (pinfunction "1_1") (pintype "passive"))
      (node (ref "C38") (pin "1") (pinfunction "1_1") (pintype "passive"))
      (node (ref "C39") (pin "1") (pinfunction "1_1") (pintype "passive"))
      (node (ref "C40") (pin "1") (pinfunction "1_1") (pintype "passive"))
      (node (ref "C41") (pin "1") (pinfunction "1_1") (pintype "passive"))
      (node (ref "C50") (pin "2") (pinfunction "2_2") (pintype "passive"))
      (node (ref "C51") (pin "1") (pinfunction "1_1") (pintype "passive"))
      (node (ref "C52") (pin "1") (pinfunction "1_1") (pintype "passive"))
      (node (ref "C53") (pin "1") (pinfunction "1_1") (pintype "passive"))
      (node (ref "C54") (pin "1") (pinfunction "1_1") (pintype "passive"))
      (node (ref "C55") (pin "1") (pinfunction "1_1") (pintype "passive"))
      (node (ref "C66") (pin "1") (pinfunction "1_1") (pintype "passive"))
      (node (ref "C67") (pin "1") (pinfunction "1_1") (pintype "passive"))
      (node (ref "C68") (pin "1") (pinfunction "1_1") (pintype "passive"))
      (node (ref "C69") (pin "1") (pinfunction "1_1") (pintype "passive"))
      (node (ref "C74") (pin "1") (pinfunction "1_1") (pintype "passive"))
      (node (ref "C75") (pin "1") (pinfunction "1_1") (pintype "passive"))
      (node (ref "C76") (pin "2") (pinfunction "2_2") (pintype "passive"))
      (node (ref "C77") (pin "2") (pinfunction "2_2") (pintype "passive"))
      (node (ref "C78") (pin "2") (pinfunction "2_2") (pintype "passive"))
      (node (ref "C79") (pin "2") (pinfunction "2_2") (pintype "passive"))
      (node (ref "C80") (pin "1") (pinfunction "1_1") (pintype "passive"))
      (node (ref "C81") (pin "1") (pinfunction "1_1") (pintype "passive"))
      (node (ref "C82") (pin "2") (pinfunction "2_2") (pintype "passive"))
      (node (ref "C83") (pin "2") (pinfunction "2_2") (pintype "passive"))
      (node (ref "C84") (pin "1") (pinfunction "1_1") (pintype "passive"))
      (node (ref "C91") (pin "2") (pinfunction "2_2") (pintype "passive"))
      (node (ref "D11") (pin "2") (pintype "passive"))
      (node (ref "D7") (pin "2") (pintype "passive"))
      (node (ref "D8") (pin "2") (pintype "passive"))
      (node (ref "Q1") (pin "E") (pinfunction "E_E") (pintype "passive"))
      (node (ref "Q2") (pin "E") (pinfunction "E_E") (pintype "passive"))
      (node (ref "R21") (pin "2") (pinfunction "2_2") (pintype "passive"))
      (node (ref "R36") (pin "1") (pinfunction "1_1") (pintype "passive"))
      (node (ref "R41") (pin "2") (pinfunction "2_2") (pintype "passive"))
      (node (ref "R54") (pin "1") (pinfunction "1_1") (pintype "passive"))
      (node (ref "R59") (pin "1") (pinfunction "1_1") (pintype "passive"))
      (node (ref "R61") (pin "2") (pinfunction "2_2") (pintype "passive"))
      (node (ref "U16") (pin "10") (pinfunction "MCT_10") (pintype "passive"))
      (node (ref "U16") (pin "S1") (pinfunction "SHIELD_S1") (pintype "passive"))
      (node (ref "U16") (pin "S2") (pinfunction "SHIELD_S2") (pintype "passive"))
      (node (ref "U17") (pin "2") (pinfunction "GND_2") (pintype "passive"))
      (node (ref "U17") (pin "3") (pinfunction "GND_3") (pintype "passive"))
      (node (ref "U17") (pin "4") (pinfunction "GND_4") (pintype "passive"))
      (node (ref "U18") (pin "2") (pinfunction "GND_2") (pintype "passive"))
      (node (ref "U18") (pin "3") (pinfunction "GND_3") (pintype "passive"))
      (node (ref "U18") (pin "4") (pinfunction "GND_4") (pintype "passive"))
      (node (ref "U19") (pin "1") (pinfunction "1_1") (pintype "passive"))
      (node (ref "U19") (pin "2") (pinfunction "2_2") (pintype "passive"))
      (node (ref "U19") (pin "3") (pinfunction "3_3") (pintype "passive"))
      (node (ref "U19") (pin "4") (pinfunction "4_4") (pintype "passive"))
      (node (ref "U19") (pin "C5") (pinfunction "GND_C5") (pintype "passive"))
      (node (ref "U2") (pin "3") (pinfunction "GND_3") (pintype "passive"))
      (node (ref "U2") (pin "8") (pinfunction "GND_8") (pintype "passive"))
      (node (ref "U20") (pin "2") (pinfunction "GND_2") (pintype "passive"))
      (node (ref "U20") (pin "3") (pinfunction "GND_3") (pintype "passive"))
      (node (ref "U20") (pin "4") (pinfunction "GND_4") (pintype "passive"))
      (node (ref "U22") (pin "11") (pinfunction "TMDSClockSchield_11") (pintype "passive"))
      (node (ref "U22") (pin "17") (pinfunction "DDC/CECGround_17") (pintype "passive"))
      (node (ref "U22") (pin "2") (pinfunction "TMDSData2Shield_2") (pintype "passive"))
      (node (ref "U22") (pin "5") (pinfunction "TMDSData1Shield_5") (pintype "passive"))
      (node (ref "U22") (pin "8") (pinfunction "TMDSData0Shield_8") (pintype "passive"))
      (node (ref "U22") (pin "S1") (pinfunction "S_S1") (pintype "passive"))
      (node (ref "U22") (pin "S2") (pinfunction "S_S2") (pintype "passive"))
      (node (ref "U22") (pin "S3") (pinfunction "S_S3") (pintype "passive"))
      (node (ref "U22") (pin "S4") (pinfunction "S_S4") (pintype "passive"))
      (node (ref "U23") (pin "3") (pinfunction "GND_3") (pintype "passive"))
      (node (ref "U23") (pin "8") (pinfunction "GND_8") (pintype "passive"))
      (node (ref "U24") (pin "15") (pinfunction "GND_15") (pintype "passive"))
      (node (ref "U24") (pin "18") (pinfunction "GND_18") (pintype "passive"))
      (node (ref "U24") (pin "21") (pinfunction "GND_21") (pintype "passive"))
      (node (ref "U24") (pin "26") (pinfunction "GND_26") (pintype "passive"))
      (node (ref "U24") (pin "27") (pinfunction "GND_27") (pintype "passive"))
      (node (ref "U24") (pin "29") (pinfunction "GND_29") (pintype "passive"))
      (node (ref "U24") (pin "34") (pinfunction "GND_34") (pintype "passive"))
      (node (ref "U24") (pin "35") (pinfunction "GND_35") (pintype "passive"))
      (node (ref "U24") (pin "37") (pinfunction "GND_37") (pintype "passive"))
      (node (ref "U24") (pin "4") (pinfunction "GND_4") (pintype "passive"))
      (node (ref "U24") (pin "40") (pinfunction "GND_40") (pintype "passive"))
      (node (ref "U24") (pin "43") (pinfunction "GND_43") (pintype "passive"))
      (node (ref "U24") (pin "50") (pinfunction "GND_50") (pintype "passive"))
      (node (ref "U24") (pin "53") (pinfunction "53_53") (pintype "passive"))
      (node (ref "U24") (pin "54") (pinfunction "54_54") (pintype "passive"))
      (node (ref "U24") (pin "55") (pinfunction "55_55") (pintype "passive"))
      (node (ref "U24") (pin "56") (pinfunction "56_56") (pintype "passive"))
      (node (ref "U24") (pin "9") (pinfunction "GND_9") (pintype "passive"))
      (node (ref "U25") (pin "15") (pinfunction "GND_15") (pintype "passive"))
      (node (ref "U25") (pin "18") (pinfunction "GND_18") (pintype "passive"))
      (node (ref "U25") (pin "21") (pinfunction "GND_21") (pintype "passive"))
      (node (ref "U25") (pin "26") (pinfunction "GND_26") (pintype "passive"))
      (node (ref "U25") (pin "27") (pinfunction "GND_27") (pintype "passive"))
      (node (ref "U25") (pin "29") (pinfunction "GND_29") (pintype "passive"))
      (node (ref "U25") (pin "34") (pinfunction "GND_34") (pintype "passive"))
      (node (ref "U25") (pin "35") (pinfunction "GND_35") (pintype "passive"))
      (node (ref "U25") (pin "37") (pinfunction "GND_37") (pintype "passive"))
      (node (ref "U25") (pin "4") (pinfunction "GND_4") (pintype "passive"))
      (node (ref "U25") (pin "40") (pinfunction "GND_40") (pintype "passive"))
      (node (ref "U25") (pin "43") (pinfunction "GND_43") (pintype "passive"))
      (node (ref "U25") (pin "50") (pinfunction "GND_50") (pintype "passive"))
      (node (ref "U25") (pin "53") (pinfunction "53_53") (pintype "passive"))
      (node (ref "U25") (pin "54") (pinfunction "54_54") (pintype "passive"))
      (node (ref "U25") (pin "55") (pinfunction "55_55") (pintype "passive"))
      (node (ref "U25") (pin "56") (pinfunction "56_56") (pintype "passive"))
      (node (ref "U25") (pin "9") (pinfunction "GND_9") (pintype "passive"))
      (node (ref "U26") (pin "1") (pinfunction "GND_1") (pintype "passive"))
      (node (ref "U26") (pin "12") (pinfunction "GND_12") (pintype "passive"))
      (node (ref "U26") (pin "14") (pinfunction "GND_14") (pintype "passive"))
      (node (ref "U26") (pin "15") (pinfunction "GND_15") (pintype "passive"))
      (node (ref "U26") (pin "16") (pinfunction "GND_16") (pintype "passive"))
      (node (ref "U27") (pin "3") (pinfunction "GND_3") (pintype "passive"))
      (node (ref "U27") (pin "8") (pinfunction "GND_8") (pintype "passive"))
      (node (ref "U28") (pin "1") (pinfunction "GND_1") (pintype "passive"))
      (node (ref "U28") (pin "10") (pinfunction "GND_10") (pintype "passive"))
      (node (ref "U28") (pin "12") (pinfunction "GND_12") (pintype "passive"))
      (node (ref "U29") (pin "5") (pinfunction "GND_5") (pintype "passive"))
      (node (ref "U31") (pin "3") (pintype "passive"))
      (node (ref "U32") (pin "1") (pinfunction "GND_1") (pintype "passive"))
      (node (ref "U34") (pin "3") (pinfunction "G_3") (pintype "passive"))
      (node (ref "U42") (pin "12") (pinfunction "12_12") (pintype "passive"))
      (node (ref "U42") (pin "15") (pinfunction "15_15") (pintype "passive"))
      (node (ref "U42") (pin "16") (pinfunction "16_16") (pintype "passive"))
      (node (ref "U42") (pin "17") (pinfunction "17_17") (pintype "passive"))
      (node (ref "U42") (pin "6") (pinfunction "6_6") (pintype "passive"))
      (node (ref "U42") (pin "9") (pinfunction "9_9") (pintype "passive"))
      (node (ref "U46") (pin "3") (pinfunction "GND_3") (pintype "passive"))
      (node (ref "U46") (pin "8") (pinfunction "GND_8") (pintype "passive"))
      (node (ref "U47") (pin "3") (pinfunction "GND_3") (pintype "passive"))
      (node (ref "U47") (pin "8") (pinfunction "GND_8") (pintype "passive"))
      (node (ref "U48") (pin "3") (pinfunction "GND_3") (pintype "passive"))
      (node (ref "U48") (pin "8") (pinfunction "GND_8") (pintype "passive"))
    )
    (net (code "71") (name "Net-(C35-Pad2)") (class "Default")
      (node (ref "C35") (pin "2") (pinfunction "2_2") (pintype "passive"))
      (node (ref "U16") (pin "1") (pinfunction "MCT_1") (pintype "passive"))
    )
    (net (code "72") (name "Net-(C84-Pad2)") (class "Default")
      (node (ref "C84") (pin "2") (pinfunction "2_2") (pintype "passive"))
      (node (ref "Q1") (pin "B") (pinfunction "B_B") (pintype "passive"))
      (node (ref "R17") (pin "2") (pinfunction "2_2") (pintype "passive"))
    )
    (net (code "73") (name "Net-(D8-Pad1)") (class "Default")
      (node (ref "D8") (pin "1") (pintype "passive"))
      (node (ref "R3") (pin "2") (pinfunction "2_2") (pintype "passive"))
    )
    (net (code "74") (name "Net-(D9-Pad2)") (class "Default")
      (node (ref "D9") (pin "2") (pintype "passive"))
      (node (ref "R21") (pin "1") (pinfunction "1_1") (pintype "passive"))
    )
    (net (code "75") (name "Net-(D10-Pad1)") (class "Default")
      (node (ref "D10") (pin "1") (pintype "passive"))
      (node (ref "R60") (pin "1") (pinfunction "1_1") (pintype "passive"))
    )
    (net (code "76") (name "Net-(D10-Pad2)") (class "Default")
      (node (ref "D10") (pin "2") (pintype "passive"))
      (node (ref "Q4") (pin "C") (pinfunction "C_C") (pintype "passive"))
    )
    (net (code "77") (name "Net-(D11-Pad1)") (class "Default")
      (node (ref "D11") (pin "1") (pintype "passive"))
      (node (ref "R77") (pin "2") (pinfunction "2_2") (pintype "passive"))
    )
    (net (code "78") (name "Net-(L4-Pad1)") (class "Default")
      (node (ref "L4") (pin "1") (pinfunction "1_1") (pintype "passive"))
      (node (ref "R52") (pin "2") (pinfunction "2_2") (pintype "passive"))
    )
    (net (code "79") (name "Net-(Q2-PadB)") (class "Default")
      (node (ref "Q2") (pin "B") (pinfunction "B_B") (pintype "passive"))
      (node (ref "R58") (pin "2") (pinfunction "2_2") (pintype "passive"))
      (node (ref "R59") (pin "2") (pinfunction "2_2") (pintype "passive"))
    )
    (net (code "80") (name "Net-(Q4-PadB)") (class "Default")
      (node (ref "Q4") (pin "B") (pinfunction "B_B") (pintype "passive"))
      (node (ref "Q4") (pin "E") (pinfunction "E_E") (pintype "passive"))
      (node (ref "R18") (pin "2") (pinfunction "2_2") (pintype "passive"))
      (node (ref "R36") (pin "2") (pinfunction "2_2") (pintype "passive"))
    )
    (net (code "81") (name "Net-(R20-Pad2)") (class "Default")
      (node (ref "R20") (pin "2") (pinfunction "2_2") (pintype "passive"))
      (node (ref "U16") (pin "11") (pinfunction "11_11") (pintype "passive"))
    )
    (net (code "82") (name "Net-(R23-Pad2)") (class "Default")
      (node (ref "R23") (pin "2") (pinfunction "2_2") (pintype "passive"))
      (node (ref "U16") (pin "14") (pinfunction "14_14") (pintype "passive"))
    )
    (net (code "83") (name "Net-(U24-PERST1#)") (class "Default")
      (node (ref "R19") (pin "2") (pinfunction "2_2") (pintype "passive"))
      (node (ref "U24") (pin "22") (pinfunction "PERST1#_22") (pintype "passive"))
    )
    (net (code "84") (name "Net-(U25-PERST1#)") (class "Default")
      (node (ref "Q1") (pin "C") (pinfunction "C_C") (pintype "passive"))
      (node (ref "U25") (pin "22") (pinfunction "PERST1#_22") (pintype "passive"))
    )
    (net (code "85") (name "Net-(U25-UIM_CLK)") (class "Default")
      (node (ref "R32") (pin "1") (pinfunction "1_1") (pintype "passive"))
      (node (ref "U25") (pin "12") (pinfunction "UIM_CLK_12") (pintype "passive"))
    )
    (net (code "86") (name "Net-(U25-UIM_DATA)") (class "Default")
      (node (ref "R30") (pin "1") (pinfunction "1_1") (pintype "passive"))
      (node (ref "U25") (pin "10") (pinfunction "UIM_DATA_10") (pintype "passive"))
    )
    (net (code "87") (name "Net-(U25-UIM_RESET)") (class "Default")
      (node (ref "R33") (pin "1") (pinfunction "1_1") (pintype "passive"))
      (node (ref "U25") (pin "14") (pinfunction "UIM_RESET_14") (pintype "passive"))
    )
    (net (code "88") (name "Net-(U25-USB_D+)") (class "Default")
      (node (ref "R28") (pin "1") (pinfunction "1_1") (pintype "passive"))
      (node (ref "U25") (pin "38") (pinfunction "USB_D+_38") (pintype "passive"))
    )
    (net (code "89") (name "Net-(U25-USB_D-)") (class "Default")
      (node (ref "R22") (pin "2") (pinfunction "2_2") (pintype "passive"))
      (node (ref "U25") (pin "36") (pinfunction "USB_D-_36") (pintype "passive"))
    )
    (net (code "90") (name "Net-(U28-RESET)") (class "Default")
      (node (ref "Q2") (pin "C") (pinfunction "C_C") (pintype "passive"))
      (node (ref "U28") (pin "9") (pinfunction "RESET_9") (pintype "passive"))
    )
    (net (code "91") (name "Net-(U28-RF_IN)") (class "Default")
      (node (ref "R55") (pin "1") (pinfunction "1_1") (pintype "passive"))
      (node (ref "U28") (pin "11") (pinfunction "RF_IN_11") (pintype "passive"))
    )
    (net (code "92") (name "Net-(U28-RXD1)") (class "Default")
      (node (ref "R47") (pin "2") (pinfunction "2_2") (pintype "passive"))
      (node (ref "U28") (pin "3") (pinfunction "RXD1_3") (pintype "passive"))
    )
    (net (code "93") (name "Net-(U28-STANDBY)") (class "Default")
      (node (ref "R49") (pin "2") (pinfunction "2_2") (pintype "passive"))
      (node (ref "U28") (pin "5") (pinfunction "STANDBY_5") (pintype "passive"))
    )
    (net (code "94") (name "Net-(U28-TIMER)") (class "Default")
      (node (ref "R41") (pin "1") (pinfunction "1_1") (pintype "passive"))
      (node (ref "U28") (pin "18") (pinfunction "TIMER_18") (pintype "passive"))
    )
    (net (code "95") (name "Net-(U28-TXD1)") (class "Default")
      (node (ref "R44") (pin "2") (pinfunction "2_2") (pintype "passive"))
      (node (ref "U28") (pin "2") (pinfunction "TXD1_2") (pintype "passive"))
    )
    (net (code "96") (name "Net-(U28-VCC_RF)") (class "Default")
      (node (ref "R52") (pin "1") (pinfunction "1_1") (pintype "passive"))
      (node (ref "U28") (pin "14") (pinfunction "VCC_RF_14") (pintype "passive"))
    )
    (net (code "97") (name "Net-(U28-V_BCKP)") (class "Default")
      (node (ref "R53") (pin "2") (pinfunction "2_2") (pintype "passive"))
      (node (ref "U28") (pin "6") (pinfunction "V_BCKP_6") (pintype "passive"))
    )
    (net (code "98") (name "Net-(U29-A)") (class "Default")
      (node (ref "R50") (pin "2") (pinfunction "2_2") (pintype "passive"))
      (node (ref "R51") (pin "2") (pinfunction "2_2") (pintype "passive"))
      (node (ref "U29") (pin "6") (pinfunction "A_6") (pintype "passive"))
      (node (ref "U30") (pin "2") (pinfunction "A_2") (pintype "passive"))
      (node (ref "U31") (pin "1") (pintype "passive"))
    )
    (net (code "99") (name "Net-(U29-B)") (class "Default")
      (node (ref "R50") (pin "1") (pinfunction "1_1") (pintype "passive"))
      (node (ref "R61") (pin "1") (pinfunction "1_1") (pintype "passive"))
      (node (ref "U29") (pin "7") (pinfunction "B_7") (pintype "passive"))
      (node (ref "U30") (pin "1") (pinfunction "B_1") (pintype "passive"))
      (node (ref "U31") (pin "2") (pintype "passive"))
    )
    (net (code "100") (name "Net-(U29-DI)") (class "Default")
      (node (ref "R48") (pin "2") (pinfunction "2_2") (pintype "passive"))
      (node (ref "U29") (pin "4") (pinfunction "DI_4") (pintype "passive"))
    )
    (net (code "101") (name "Net-(U29-RO)") (class "Default")
      (node (ref "R42") (pin "2") (pinfunction "2_2") (pintype "passive"))
      (node (ref "U29") (pin "1") (pinfunction "RO_1") (pintype "passive"))
    )
    (net (code "102") (name "Net-(U29-VCC)") (class "Default")
      (node (ref "C78") (pin "1") (pinfunction "1_1") (pintype "passive"))
      (node (ref "C79") (pin "1") (pinfunction "1_1") (pintype "passive"))
      (node (ref "R43") (pin "1") (pinfunction "1_1") (pintype "passive"))
      (node (ref "U29") (pin "8") (pinfunction "VCC_8") (pintype "passive"))
    )
    (net (code "103") (name "Net-(U32-P1.2)") (class "Default")
      (node (ref "R46") (pin "1") (pinfunction "1_1") (pintype "passive"))
      (node (ref "U32") (pin "13") (pinfunction "P1.2_13") (pintype "passive"))
    )
    (net (code "104") (name "Net-(U32-P1.3)") (class "Default")
      (node (ref "R45") (pin "1") (pinfunction "1_1") (pintype "passive"))
      (node (ref "U32") (pin "12") (pinfunction "P1.3_12") (pintype "passive"))
    )
    (net (code "105") (name "Net-(U32-P1.4)") (class "Default")
      (node (ref "R62") (pin "1") (pinfunction "1_1") (pintype "passive"))
      (node (ref "U32") (pin "11") (pinfunction "P1.4_11") (pintype "passive"))
    )
    (net (code "106") (name "Net-(U32-P1.5)") (class "Default")
      (node (ref "R63") (pin "1") (pinfunction "1_1") (pintype "passive"))
      (node (ref "U32") (pin "10") (pinfunction "P1.5_10") (pintype "passive"))
    )
    (net (code "107") (name "Net-(U32-RESET)") (class "Default")
      (node (ref "R57") (pin "1") (pinfunction "1_1") (pintype "passive"))
      (node (ref "U32") (pin "24") (pinfunction "RESET_24") (pintype "passive"))
    )
    (net (code "108") (name "Net-(U34-R)") (class "Default")
      (node (ref "R67") (pin "1") (pinfunction "1_1") (pintype "passive"))
      (node (ref "U34") (pin "2") (pinfunction "R_2") (pintype "passive"))
    )
    (net (code "109") (name "Net-(U34-T)") (class "Default")
      (node (ref "R64") (pin "1") (pinfunction "1_1") (pintype "passive"))
      (node (ref "U34") (pin "1") (pinfunction "T_1") (pintype "passive"))
    )
    (net (code "110") (name "PWR_3V3") (class "Default")
      (node (ref "C106") (pin "1") (pinfunction "1_1") (pintype "passive"))
      (node (ref "C50") (pin "1") (pinfunction "1_1") (pintype "passive"))
      (node (ref "C51") (pin "2") (pinfunction "2_2") (pintype "passive"))
      (node (ref "C52") (pin "2") (pinfunction "2_2") (pintype "passive"))
      (node (ref "C53") (pin "2") (pinfunction "2_2") (pintype "passive"))
      (node (ref "C54") (pin "2") (pinfunction "2_2") (pintype "passive"))
      (node (ref "C55") (pin "2") (pinfunction "2_2") (pintype "passive"))
      (node (ref "C76") (pin "1") (pinfunction "1_1") (pintype "passive"))
      (node (ref "C77") (pin "1") (pinfunction "1_1") (pintype "passive"))
      (node (ref "C80") (pin "2") (pinfunction "2_2") (pintype "passive"))
      (node (ref "C81") (pin "2") (pinfunction "2_2") (pintype "passive"))
      (node (ref "C82") (pin "1") (pinfunction "1_1") (pintype "passive"))
      (node (ref "C83") (pin "1") (pinfunction "1_1") (pintype "passive"))
      (node (ref "C91") (pin "1") (pinfunction "1_1") (pintype "passive"))
      (node (ref "R20") (pin "1") (pinfunction "1_1") (pintype "passive"))
      (node (ref "R23") (pin "1") (pinfunction "1_1") (pintype "passive"))
      (node (ref "R43") (pin "2") (pinfunction "2_2") (pintype "passive"))
      (node (ref "R49") (pin "1") (pinfunction "1_1") (pintype "passive"))
      (node (ref "R51") (pin "1") (pinfunction "1_1") (pintype "passive"))
      (node (ref "R53") (pin "1") (pinfunction "1_1") (pintype "passive"))
      (node (ref "R56") (pin "1") (pinfunction "1_1") (pintype "passive"))
      (node (ref "R60") (pin "2") (pinfunction "2_2") (pintype "passive"))
      (node (ref "R74") (pin "2") (pinfunction "2_2") (pintype "passive"))
      (node (ref "R75") (pin "2") (pinfunction "2_2") (pintype "passive"))
      (node (ref "U24") (pin "2") (pinfunction "VCC_2") (pintype "passive"))
      (node (ref "U24") (pin "24") (pinfunction "VCC_24") (pintype "passive"))
      (node (ref "U24") (pin "39") (pinfunction "VCC_39") (pintype "passive"))
      (node (ref "U24") (pin "41") (pinfunction "VCC_41") (pintype "passive"))
      (node (ref "U24") (pin "52") (pinfunction "VCC_52") (pintype "passive"))
      (node (ref "U26") (pin "11") (pinfunction "VCC_11") (pintype "passive"))
      (node (ref "U28") (pin "8") (pinfunction "VCC_8") (pintype "passive"))
      (node (ref "U32") (pin "2") (pinfunction "VCC_2") (pintype "passive"))
      (node (ref "U42") (pin "1") (pinfunction "1_1") (pintype "passive"))
    )
    (net (code "111") (name "PWR_3V8") (class "Default")
      (node (ref "C124") (pin "1") (pinfunction "1_1") (pintype "passive"))
      (node (ref "C24") (pin "1") (pinfunction "1_1") (pintype "passive"))
      (node (ref "C36") (pin "1") (pinfunction "1_1") (pintype "passive"))
      (node (ref "C37") (pin "2") (pinfunction "2_2") (pintype "passive"))
      (node (ref "C38") (pin "2") (pinfunction "2_2") (pintype "passive"))
      (node (ref "C39") (pin "2") (pinfunction "2_2") (pintype "passive"))
      (node (ref "C40") (pin "2") (pinfunction "2_2") (pintype "passive"))
      (node (ref "C41") (pin "2") (pinfunction "2_2") (pintype "passive"))
      (node (ref "U25") (pin "2") (pinfunction "VCC_2") (pintype "passive"))
      (node (ref "U25") (pin "24") (pinfunction "VCC_24") (pintype "passive"))
      (node (ref "U25") (pin "39") (pinfunction "VCC_39") (pintype "passive"))
      (node (ref "U25") (pin "41") (pinfunction "VCC_41") (pintype "passive"))
      (node (ref "U25") (pin "52") (pinfunction "VCC_52") (pintype "passive"))
    )
    (net (code "112") (name "PWR_5V") (class "Default")
      (node (ref "C110") (pin "1") (pinfunction "1_1") (pintype "passive"))
      (node (ref "C74") (pin "2") (pinfunction "2_2") (pintype "passive"))
      (node (ref "C75") (pin "2") (pinfunction "2_2") (pintype "passive"))
      (node (ref "U22") (pin "18") (pinfunction "+5V_18") (pintype "passive"))
    )
    (net (code "113") (name "VDD_EXT") (class "Default")
      (node (ref "R35") (pin "1") (pinfunction "1_1") (pintype "passive"))
      (node (ref "U25") (pin "11") (pinfunction "REFCLK-_11") (pintype "passive"))
    )
    (net (code "114") (name "unconnected-(U19-VPP-PadC6)") (class "Default")
      (node (ref "U19") (pin "C6") (pinfunction "VPP_C6") (pintype "passive+no_connect"))
    )
    (net (code "115") (name "unconnected-(U22-Reserved-Pad14)") (class "Default")
      (node (ref "U22") (pin "14") (pinfunction "Reserved_14") (pintype "passive+no_connect"))
    )
    (net (code "116") (name "unconnected-(U24-1.5V-Pad6)") (class "Default")
      (node (ref "U24") (pin "6") (pinfunction "1.5V_6") (pintype "passive+no_connect"))
    )
    (net (code "117") (name "unconnected-(U24-1.5V-Pad28)") (class "Default")
      (node (ref "U24") (pin "28") (pinfunction "1.5V_28") (pintype "passive+no_connect"))
    )
    (net (code "118") (name "unconnected-(U24-1.5V-Pad48)") (class "Default")
      (node (ref "U24") (pin "48") (pinfunction "1.5V_48") (pintype "passive+no_connect"))
    )
    (net (code "119") (name "unconnected-(U24-CLKREQ#-Pad7)") (class "Default")
      (node (ref "U24") (pin "7") (pinfunction "CLKREQ#_7") (pintype "passive+no_connect"))
    )
    (net (code "120") (name "unconnected-(U24-COEX1-Pad3)") (class "Default")
      (node (ref "U24") (pin "3") (pinfunction "COEX1_3") (pintype "passive+no_connect"))
    )
    (net (code "121") (name "unconnected-(U24-COEX2-Pad5)") (class "Default")
      (node (ref "U24") (pin "5") (pinfunction "COEX2_5") (pintype "passive+no_connect"))
    )
    (net (code "122") (name "unconnected-(U24-LED_WLAN#-Pad44)") (class "Default")
      (node (ref "U24") (pin "44") (pinfunction "LED_WLAN#_44") (pintype "passive+no_connect"))
    )
    (net (code "123") (name "unconnected-(U24-LED_WWAN#-Pad42)") (class "Default")
      (node (ref "U24") (pin "42") (pinfunction "LED_WWAN#_42") (pintype "passive+no_connect"))
    )
    (net (code "124") (name "unconnected-(U24-PERn0-Pad23)") (class "Default")
      (node (ref "U24") (pin "23") (pinfunction "PERn0_23") (pintype "passive+no_connect"))
    )
    (net (code "125") (name "unconnected-(U24-PERp0-Pad25)") (class "Default")
      (node (ref "U24") (pin "25") (pinfunction "PERp0_25") (pintype "passive+no_connect"))
    )
    (net (code "126") (name "unconnected-(U24-PETn0-Pad31)") (class "Default")
      (node (ref "U24") (pin "31") (pinfunction "PETn0_31") (pintype "passive+no_connect"))
    )
    (net (code "127") (name "unconnected-(U24-PETp0-Pad33)") (class "Default")
      (node (ref "U24") (pin "33") (pinfunction "PETp0_33") (pintype "passive+no_connect"))
    )
    (net (code "128") (name "unconnected-(U24-REFCLK+-Pad13)") (class "Default")
      (node (ref "U24") (pin "13") (pinfunction "REFCLK+_13") (pintype "passive+no_connect"))
    )
    (net (code "129") (name "unconnected-(U24-REFCLK--Pad11)") (class "Default")
      (node (ref "U24") (pin "11") (pinfunction "REFCLK-_11") (pintype "passive+no_connect"))
    )
    (net (code "130") (name "unconnected-(U24-RESERVED-Pad17)") (class "Default")
      (node (ref "U24") (pin "17") (pinfunction "RESERVED_17") (pintype "passive+no_connect"))
    )
    (net (code "131") (name "unconnected-(U24-SMB_DATA-Pad30)") (class "Default")
      (node (ref "U24") (pin "30") (pinfunction "SMB_DATA_30") (pintype "passive+no_connect"))
    )
    (net (code "132") (name "unconnected-(U24-SMB_DATA-Pad32)") (class "Default")
      (node (ref "U24") (pin "32") (pinfunction "SMB_DATA_32") (pintype "passive+no_connect"))
    )
    (net (code "133") (name "unconnected-(U24-UIM_CLK-Pad12)") (class "Default")
      (node (ref "U24") (pin "12") (pinfunction "UIM_CLK_12") (pintype "passive+no_connect"))
    )
    (net (code "134") (name "unconnected-(U24-UIM_DATA-Pad10)") (class "Default")
      (node (ref "U24") (pin "10") (pinfunction "UIM_DATA_10") (pintype "passive+no_connect"))
    )
    (net (code "135") (name "unconnected-(U24-UIM_PWR-Pad8)") (class "Default")
      (node (ref "U24") (pin "8") (pinfunction "UIM_PWR_8") (pintype "passive+no_connect"))
    )
    (net (code "136") (name "unconnected-(U24-UIM_RESET-Pad14)") (class "Default")
      (node (ref "U24") (pin "14") (pinfunction "UIM_RESET_14") (pintype "passive+no_connect"))
    )
    (net (code "137") (name "unconnected-(U24-UIM_VPP-Pad16)") (class "Default")
      (node (ref "U24") (pin "16") (pinfunction "UIM_VPP_16") (pintype "passive+no_connect"))
    )
    (net (code "138") (name "unconnected-(U24-USB_D+-Pad38)") (class "Default")
      (node (ref "U24") (pin "38") (pinfunction "USB_D+_38") (pintype "passive+no_connect"))
    )
    (net (code "139") (name "unconnected-(U24-USB_D--Pad36)") (class "Default")
      (node (ref "U24") (pin "36") (pinfunction "USB_D-_36") (pintype "passive+no_connect"))
    )
    (net (code "140") (name "unconnected-(U24-WAKE#-Pad1)") (class "Default")
      (node (ref "U24") (pin "1") (pinfunction "WAKE#_1") (pintype "passive+no_connect"))
    )
    (net (code "141") (name "unconnected-(U24-W_DISABLE#-Pad20)") (class "Default")
      (node (ref "U24") (pin "20") (pinfunction "W_DISABLE#_20") (pintype "passive+no_connect"))
    )
    (net (code "142") (name "unconnected-(U25-1.5V-Pad6)") (class "Default")
      (node (ref "U25") (pin "6") (pinfunction "1.5V_6") (pintype "passive+no_connect"))
    )
    (net (code "143") (name "unconnected-(U25-1.5V-Pad28)") (class "Default")
      (node (ref "U25") (pin "28") (pinfunction "1.5V_28") (pintype "passive+no_connect"))
    )
    (net (code "144") (name "unconnected-(U25-1.5V-Pad48)") (class "Default")
      (node (ref "U25") (pin "48") (pinfunction "1.5V_48") (pintype "passive+no_connect"))
    )
    (net (code "145") (name "unconnected-(U25-CLKREQ#-Pad7)") (class "Default")
      (node (ref "U25") (pin "7") (pinfunction "CLKREQ#_7") (pintype "passive+no_connect"))
    )
    (net (code "146") (name "unconnected-(U25-COEX1-Pad3)") (class "Default")
      (node (ref "U25") (pin "3") (pinfunction "COEX1_3") (pintype "passive+no_connect"))
    )
    (net (code "147") (name "unconnected-(U25-COEX2-Pad5)") (class "Default")
      (node (ref "U25") (pin "5") (pinfunction "COEX2_5") (pintype "passive+no_connect"))
    )
    (net (code "148") (name "unconnected-(U25-LED_WPAN#-Pad46)") (class "Default")
      (node (ref "U25") (pin "46") (pinfunction "LED_WPAN#_46") (pintype "passive+no_connect"))
    )
    (net (code "149") (name "unconnected-(U25-PERn0-Pad23)") (class "Default")
      (node (ref "U25") (pin "23") (pinfunction "PERn0_23") (pintype "passive+no_connect"))
    )
    (net (code "150") (name "unconnected-(U25-PERp0-Pad25)") (class "Default")
      (node (ref "U25") (pin "25") (pinfunction "PERp0_25") (pintype "passive+no_connect"))
    )
    (net (code "151") (name "unconnected-(U25-PETn0-Pad31)") (class "Default")
      (node (ref "U25") (pin "31") (pinfunction "PETn0_31") (pintype "passive+no_connect"))
    )
    (net (code "152") (name "unconnected-(U25-PETp0-Pad33)") (class "Default")
      (node (ref "U25") (pin "33") (pinfunction "PETp0_33") (pintype "passive+no_connect"))
    )
    (net (code "153") (name "unconnected-(U25-REFCLK+-Pad13)") (class "Default")
      (node (ref "U25") (pin "13") (pinfunction "REFCLK+_13") (pintype "passive+no_connect"))
    )
    (net (code "154") (name "unconnected-(U25-RESERVED-Pad17)") (class "Default")
      (node (ref "U25") (pin "17") (pinfunction "RESERVED_17") (pintype "passive+no_connect"))
    )
    (net (code "155") (name "unconnected-(U25-RESERVED-Pad19)") (class "Default")
      (node (ref "U25") (pin "19") (pinfunction "RESERVED_19") (pintype "passive+no_connect"))
    )
    (net (code "156") (name "unconnected-(U25-RESERVED-Pad45)") (class "Default")
      (node (ref "U25") (pin "45") (pinfunction "RESERVED_45") (pintype "passive+no_connect"))
    )
    (net (code "157") (name "unconnected-(U25-RESERVED-Pad47)") (class "Default")
      (node (ref "U25") (pin "47") (pinfunction "RESERVED_47") (pintype "passive+no_connect"))
    )
    (net (code "158") (name "unconnected-(U25-RESERVED-Pad49)") (class "Default")
      (node (ref "U25") (pin "49") (pinfunction "RESERVED_49") (pintype "passive+no_connect"))
    )
    (net (code "159") (name "unconnected-(U25-RESERVED-Pad51)") (class "Default")
      (node (ref "U25") (pin "51") (pinfunction "RESERVED_51") (pintype "passive+no_connect"))
    )
    (net (code "160") (name "unconnected-(U25-SMB_DATA-Pad30)") (class "Default")
      (node (ref "U25") (pin "30") (pinfunction "SMB_DATA_30") (pintype "passive+no_connect"))
    )
    (net (code "161") (name "unconnected-(U25-SMB_DATA-Pad32)") (class "Default")
      (node (ref "U25") (pin "32") (pinfunction "SMB_DATA_32") (pintype "passive+no_connect"))
    )
    (net (code "162") (name "unconnected-(U25-UIM_VPP-Pad16)") (class "Default")
      (node (ref "U25") (pin "16") (pinfunction "UIM_VPP_16") (pintype "passive+no_connect"))
    )
    (net (code "163") (name "unconnected-(U25-WAKE#-Pad1)") (class "Default")
      (node (ref "U25") (pin "1") (pinfunction "WAKE#_1") (pintype "passive+no_connect"))
    )
    (net (code "164") (name "unconnected-(U25-W_DISABLE#-Pad20)") (class "Default")
      (node (ref "U25") (pin "20") (pinfunction "W_DISABLE#_20") (pintype "passive+no_connect"))
    )
    (net (code "165") (name "unconnected-(U26-GD02-Pad5)") (class "Default")
      (node (ref "U26") (pin "5") (pinfunction "GD02_5") (pintype "passive+no_connect"))
    )
    (net (code "166") (name "unconnected-(U26-NC-Pad10)") (class "Default")
      (node (ref "U26") (pin "10") (pinfunction "NC_10") (pintype "passive+no_connect"))
    )
    (net (code "167") (name "unconnected-(U28-ANTON-Pad13)") (class "Default")
      (node (ref "U28") (pin "13") (pinfunction "ANTON_13") (pintype "passive+no_connect"))
    )
    (net (code "168") (name "unconnected-(U28-RSVD{slash}NC-Pad7)") (class "Default")
      (node (ref "U28") (pin "7") (pinfunction "RSVD/NC_7") (pintype "passive+no_connect"))
    )
    (net (code "169") (name "unconnected-(U28-RSVD{slash}NC-Pad15)") (class "Default")
      (node (ref "U28") (pin "15") (pinfunction "RSVD/NC_15") (pintype "passive+no_connect"))
    )
    (net (code "170") (name "unconnected-(U28-RSVD{slash}NC-Pad16)") (class "Default")
      (node (ref "U28") (pin "16") (pinfunction "RSVD/NC_16") (pintype "passive+no_connect"))
    )
    (net (code "171") (name "unconnected-(U28-RSVD{slash}NC-Pad17)") (class "Default")
      (node (ref "U28") (pin "17") (pinfunction "RSVD/NC_17") (pintype "passive+no_connect"))
    )
    (net (code "172") (name "unconnected-(U32-NC-Pad8)") (class "Default")
      (node (ref "U32") (pin "8") (pinfunction "NC_8") (pintype "passive+no_connect"))
    )
    (net (code "173") (name "unconnected-(U32-NC-Pad9)") (class "Default")
      (node (ref "U32") (pin "9") (pinfunction "NC_9") (pintype "passive+no_connect"))
    )
    (net (code "174") (name "unconnected-(U32-P0.0-Pad23)") (class "Default")
      (node (ref "U32") (pin "23") (pinfunction "P0.0_23") (pintype "passive+no_connect"))
    )
    (net (code "175") (name "unconnected-(U32-P0.1-Pad22)") (class "Default")
      (node (ref "U32") (pin "22") (pinfunction "P0.1_22") (pintype "passive+no_connect"))
    )
    (net (code "176") (name "unconnected-(U32-P0.2-Pad21)") (class "Default")
      (node (ref "U32") (pin "21") (pinfunction "P0.2_21") (pintype "passive+no_connect"))
    )
    (net (code "177") (name "unconnected-(U32-P0.3-Pad20)") (class "Default")
      (node (ref "U32") (pin "20") (pinfunction "P0.3_20") (pintype "passive+no_connect"))
    )
    (net (code "178") (name "unconnected-(U32-P0.4-Pad19)") (class "Default")
      (node (ref "U32") (pin "19") (pinfunction "P0.4_19") (pintype "passive+no_connect"))
    )
    (net (code "179") (name "unconnected-(U32-P0.5-Pad18)") (class "Default")
      (node (ref "U32") (pin "18") (pinfunction "P0.5_18") (pintype "passive+no_connect"))
    )
    (net (code "180") (name "unconnected-(U32-P0.6-Pad17)") (class "Default")
      (node (ref "U32") (pin "17") (pinfunction "P0.6_17") (pintype "passive+no_connect"))
    )
    (net (code "181") (name "unconnected-(U32-P0.7-Pad16)") (class "Default")
      (node (ref "U32") (pin "16") (pinfunction "P0.7_16") (pintype "passive+no_connect"))
    )
    (net (code "182") (name "unconnected-(U32-P1.0-Pad15)") (class "Default")
      (node (ref "U32") (pin "15") (pinfunction "P1.0_15") (pintype "passive+no_connect"))
    )
    (net (code "183") (name "unconnected-(U32-P1.1-Pad14)") (class "Default")
      (node (ref "U32") (pin "14") (pinfunction "P1.1_14") (pintype "passive+no_connect"))
    )
    (net (code "184") (name "unconnected-(U32-P1.6-Pad7)") (class "Default")
      (node (ref "U32") (pin "7") (pinfunction "P1.6_7") (pintype "passive+no_connect"))
    )
    (net (code "185") (name "unconnected-(U32-P2.0-Pad5)") (class "Default")
      (node (ref "U32") (pin "5") (pinfunction "P2.0_5") (pintype "passive+no_connect"))
    )
    (net (code "186") (name "unconnected-(U32-P2.1-Pad4)") (class "Default")
      (node (ref "U32") (pin "4") (pinfunction "P2.1_4") (pintype "passive+no_connect"))
    )
    (net (code "187") (name "unconnected-(U32-P2.2-Pad3)") (class "Default")
      (node (ref "U32") (pin "3") (pinfunction "P2.2_3") (pintype "passive+no_connect"))
    )
    (net (code "188") (name "unconnected-(U42-Pad4)") (class "Default")
      (node (ref "U42") (pin "4") (pinfunction "4_4") (pintype "passive+no_connect"))
    )
  )
)
